# IMU_Sch.net
KiCad netlist of a schematic drawn in Altium Designer
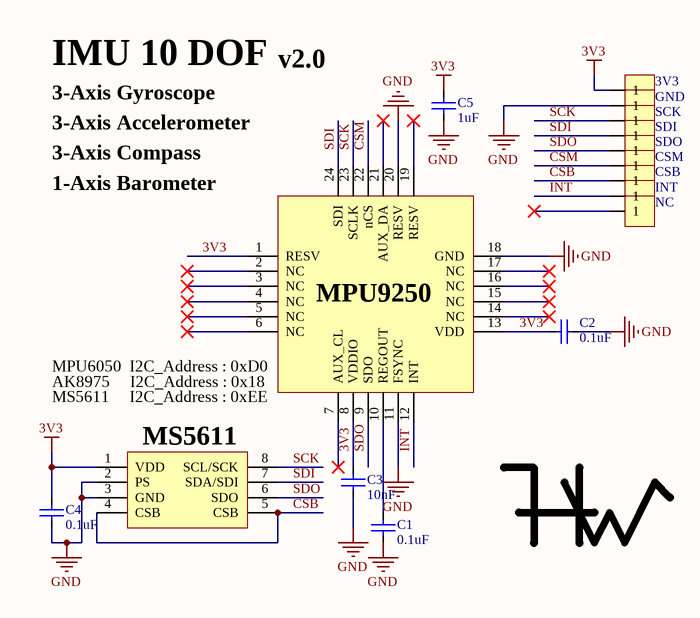
[diagram p0: IMU_Sch.SchDoc]

(export (version "E")
  (design (tool "Eeschema 10.0.6"))
  (components
    (comp (ref "3V3")
      (value "Pad1X1_1.27")
      (footprint "PCB_Connector:Pad1X1_1.27")
      (description "Header")
      (libsource (lib "SCH_Connector") (part "Pad1X1_1.27"))
    )
    (comp (ref "C1")
      (value "0.1uF")
      (footprint "PCB_Passive:CAP_0603")
      (description "Capacitor")
      (fields (field (name "Comment") "Cap_0603"))
      (libsource (lib "SCH_Passive") (part "Cap_0603"))
    )
    (comp (ref "C2")
      (value "0.1uF")
      (footprint "PCB_Passive:CAP_0603")
      (description "Capacitor")
      (fields (field (name "Comment") "Cap_0603"))
      (libsource (lib "SCH_Passive") (part "Cap_0603"))
    )
    (comp (ref "C3")
      (value "10nF")
      (footprint "PCB_Passive:CAP_0603")
      (description "Capacitor")
      (fields (field (name "Comment") "Cap_0603"))
      (libsource (lib "SCH_Passive") (part "Cap_0603"))
    )
    (comp (ref "C4")
      (value "0.1uF")
      (footprint "PCB_Passive:CAP_0603")
      (description "Capacitor")
      (fields (field (name "Comment") "Cap_0603"))
      (libsource (lib "SCH_Passive") (part "Cap_0603"))
    )
    (comp (ref "C5")
      (value "1uF")
      (footprint "PCB_Passive:CAP_0603")
      (description "Capacitor")
      (fields (field (name "Comment") "Cap_0603"))
      (libsource (lib "SCH_Passive") (part "Cap_0603"))
    )
    (comp (ref "CSB")
      (value "Pad1X1_1.27")
      (footprint "PCB_Connector:Pad1X1_1.27")
      (description "Header")
      (libsource (lib "SCH_Connector") (part "Pad1X1_1.27"))
    )
    (comp (ref "CSM")
      (value "Pad1X1_1.27")
      (footprint "PCB_Connector:Pad1X1_1.27")
      (description "Header")
      (libsource (lib "SCH_Connector") (part "Pad1X1_1.27"))
    )
    (comp (ref "GND")
      (value "Pad1X1_1.27")
      (footprint "PCB_Connector:Pad1X1_1.27")
      (description "Header")
      (libsource (lib "SCH_Connector") (part "Pad1X1_1.27"))
    )
    (comp (ref "INT")
      (value "Pad1X1_1.27")
      (footprint "PCB_Connector:Pad1X1_1.27")
      (description "Header")
      (libsource (lib "SCH_Connector") (part "Pad1X1_1.27"))
    )
    (comp (ref "Mark") (value "Mark") (footprint "PCB_Logo:Logo_HW") (libsource (lib "SCH_Mark") (part "HW")))
    (comp (ref "MPU")
      (value "MPU9250")
      (footprint "PCB_IC:MPU9250")
      (description "Sensor")
      (libsource (lib "SCH_IC") (part "MPU9250"))
    )
    (comp (ref "MS")
      (value "MS5611")
      (footprint "MS5611")
      (description "Sensor")
      (libsource (lib "SCH_IC") (part "MS5611"))
    )
    (comp (ref "NC")
      (value "Pad1X1_1.27")
      (footprint "PCB_Connector:Pad1X1_1.27")
      (description "Header")
      (libsource (lib "SCH_Connector") (part "Pad1X1_1.27"))
    )
    (comp (ref "SCK")
      (value "Pad1X1_1.27")
      (footprint "PCB_Connector:Pad1X1_1.27")
      (description "Header")
      (libsource (lib "SCH_Connector") (part "Pad1X1_1.27"))
    )
    (comp (ref "SDI")
      (value "Pad1X1_1.27")
      (footprint "PCB_Connector:Pad1X1_1.27")
      (description "Header")
      (libsource (lib "SCH_Connector") (part "Pad1X1_1.27"))
    )
    (comp (ref "SDO")
      (value "Pad1X1_1.27")
      (footprint "PCB_Connector:Pad1X1_1.27")
      (description "Header")
      (libsource (lib "SCH_Connector") (part "Pad1X1_1.27"))
    )
  )
  (nets
    (net (code "1") (name "/CSB") (class "Default")
      (node (ref "CSB") (pin "1") (pinfunction "1_1") (pintype "passive"))
      (node (ref "MS") (pin "4") (pinfunction "CSB_4") (pintype "passive"))
      (node (ref "MS") (pin "5") (pinfunction "CSB_5") (pintype "passive"))
    )
    (net (code "2") (name "/CSM") (class "Default")
      (node (ref "CSM") (pin "1") (pinfunction "1_1") (pintype "passive"))
      (node (ref "MPU") (pin "22") (pinfunction "nCS_22") (pintype "passive"))
    )
    (net (code "3") (name "/INT") (class "Default")
      (node (ref "INT") (pin "1") (pinfunction "1_1") (pintype "passive"))
      (node (ref "MPU") (pin "12") (pinfunction "INT_12") (pintype "passive"))
    )
    (net (code "4") (name "/SCK") (class "Default")
      (node (ref "MPU") (pin "23") (pinfunction "SCLK_23") (pintype "passive"))
      (node (ref "MS") (pin "8") (pinfunction "SCL/SCK_8") (pintype "passive"))
      (node (ref "SCK") (pin "1") (pinfunction "1_1") (pintype "passive"))
    )
    (net (code "5") (name "/SDI") (class "Default")
      (node (ref "MPU") (pin "24") (pinfunction "SDI_24") (pintype "passive"))
      (node (ref "MS") (pin "7") (pinfunction "SDA/SDI_7") (pintype "passive"))
      (node (ref "SDI") (pin "1") (pinfunction "1_1") (pintype "passive"))
    )
    (net (code "6") (name "/SDO") (class "Default")
      (node (ref "MPU") (pin "9") (pinfunction "SDO_9") (pintype "passive"))
      (node (ref "MS") (pin "6") (pinfunction "SDO_6") (pintype "passive"))
      (node (ref "SDO") (pin "1") (pinfunction "1_1") (pintype "passive"))
    )
    (net (code "7") (name "3V3") (class "Default")
      (node (ref "3V3") (pin "1") (pinfunction "1_1") (pintype "passive"))
      (node (ref "C2") (pin "1") (pinfunction "1_1") (pintype "passive"))
      (node (ref "C3") (pin "2") (pinfunction "2_2") (pintype "passive"))
      (node (ref "C4") (pin "1") (pinfunction "1_1") (pintype "passive"))
      (node (ref "C5") (pin "2") (pinfunction "2_2") (pintype "passive"))
      (node (ref "MPU") (pin "1") (pinfunction "RESV_1") (pintype "passive"))
      (node (ref "MPU") (pin "13") (pinfunction "VDD_13") (pintype "passive"))
      (node (ref "MPU") (pin "8") (pinfunction "VDDIO_8") (pintype "passive"))
      (node (ref "MS") (pin "1") (pinfunction "VDD_1") (pintype "passive"))
    )
    (net (code "8") (name "GND") (class "Default")
      (node (ref "C1") (pin "2") (pinfunction "2_2") (pintype "passive"))
      (node (ref "C2") (pin "2") (pinfunction "2_2") (pintype "passive"))
      (node (ref "C3") (pin "1") (pinfunction "1_1") (pintype "passive"))
      (node (ref "C4") (pin "2") (pinfunction "2_2") (pintype "passive"))
      (node (ref "C5") (pin "1") (pinfunction "1_1") (pintype "passive"))
      (node (ref "GND") (pin "1") (pinfunction "1_1") (pintype "passive"))
      (node (ref "MPU") (pin "11") (pinfunction "FSYNC_11") (pintype "passive"))
      (node (ref "MPU") (pin "18") (pinfunction "GND_18") (pintype "passive"))
      (node (ref "MPU") (pin "20") (pinfunction "RESV_20") (pintype "passive"))
      (node (ref "MS") (pin "2") (pinfunction "PS_2") (pintype "passive"))
      (node (ref "MS") (pin "3") (pinfunction "GND_3") (pintype "passive"))
    )
    (net (code "9") (name "Net-(MPU-REGOUT)") (class "Default")
      (node (ref "C1") (pin "1") (pinfunction "1_1") (pintype "passive"))
      (node (ref "MPU") (pin "10") (pinfunction "REGOUT_10") (pintype "passive"))
    )
    (net (code "10") (name "unconnected-(MPU-AUX_CL-Pad7)") (class "Default")
      (node (ref "MPU") (pin "7") (pinfunction "AUX_CL_7") (pintype "passive+no_connect"))
    )
    (net (code "11") (name "unconnected-(MPU-AUX_DA-Pad21)") (class "Default")
      (node (ref "MPU") (pin "21") (pinfunction "AUX_DA_21") (pintype "passive+no_connect"))
    )
    (net (code "12") (name "unconnected-(MPU-NC-Pad2)") (class "Default")
      (node (ref "MPU") (pin "2") (pinfunction "NC_2") (pintype "passive+no_connect"))
    )
    (net (code "13") (name "unconnected-(MPU-NC-Pad3)") (class "Default")
      (node (ref "MPU") (pin "3") (pinfunction "NC_3") (pintype "passive+no_connect"))
    )
    (net (code "14") (name "unconnected-(MPU-NC-Pad4)") (class "Default")
      (node (ref "MPU") (pin "4") (pinfunction "NC_4") (pintype "passive+no_connect"))
    )
    (net (code "15") (name "unconnected-(MPU-NC-Pad5)") (class "Default")
      (node (ref "MPU") (pin "5") (pinfunction "NC_5") (pintype "passive+no_connect"))
    )
    (net (code "16") (name "unconnected-(MPU-NC-Pad6)") (class "Default")
      (node (ref "MPU") (pin "6") (pinfunction "NC_6") (pintype "passive+no_connect"))
    )
    (net (code "17") (name "unconnected-(MPU-NC-Pad14)") (class "Default")
      (node (ref "MPU") (pin "14") (pinfunction "NC_14") (pintype "passive+no_connect"))
    )
    (net (code "18") (name "unconnected-(MPU-NC-Pad15)") (class "Default")
      (node (ref "MPU") (pin "15") (pinfunction "NC_15") (pintype "passive+no_connect"))
    )
    (net (code "19") (name "unconnected-(MPU-NC-Pad16)") (class "Default")
      (node (ref "MPU") (pin "16") (pinfunction "NC_16") (pintype "passive+no_connect"))
    )
    (net (code "20") (name "unconnected-(MPU-NC-Pad17)") (class "Default")
      (node (ref "MPU") (pin "17") (pinfunction "NC_17") (pintype "passive+no_connect"))
    )
    (net (code "21") (name "unconnected-(MPU-RESV-Pad19)") (class "Default")
      (node (ref "MPU") (pin "19") (pinfunction "RESV_19") (pintype "passive+no_connect"))
    )
    (net (code "22") (name "unconnected-(NC-Pad1)") (class "Default")
      (node (ref "NC") (pin "1") (pinfunction "1_1") (pintype "passive+no_connect"))
    )
  )
)
